# Servos.net
KiCad netlist of a schematic drawn in Altium Designer
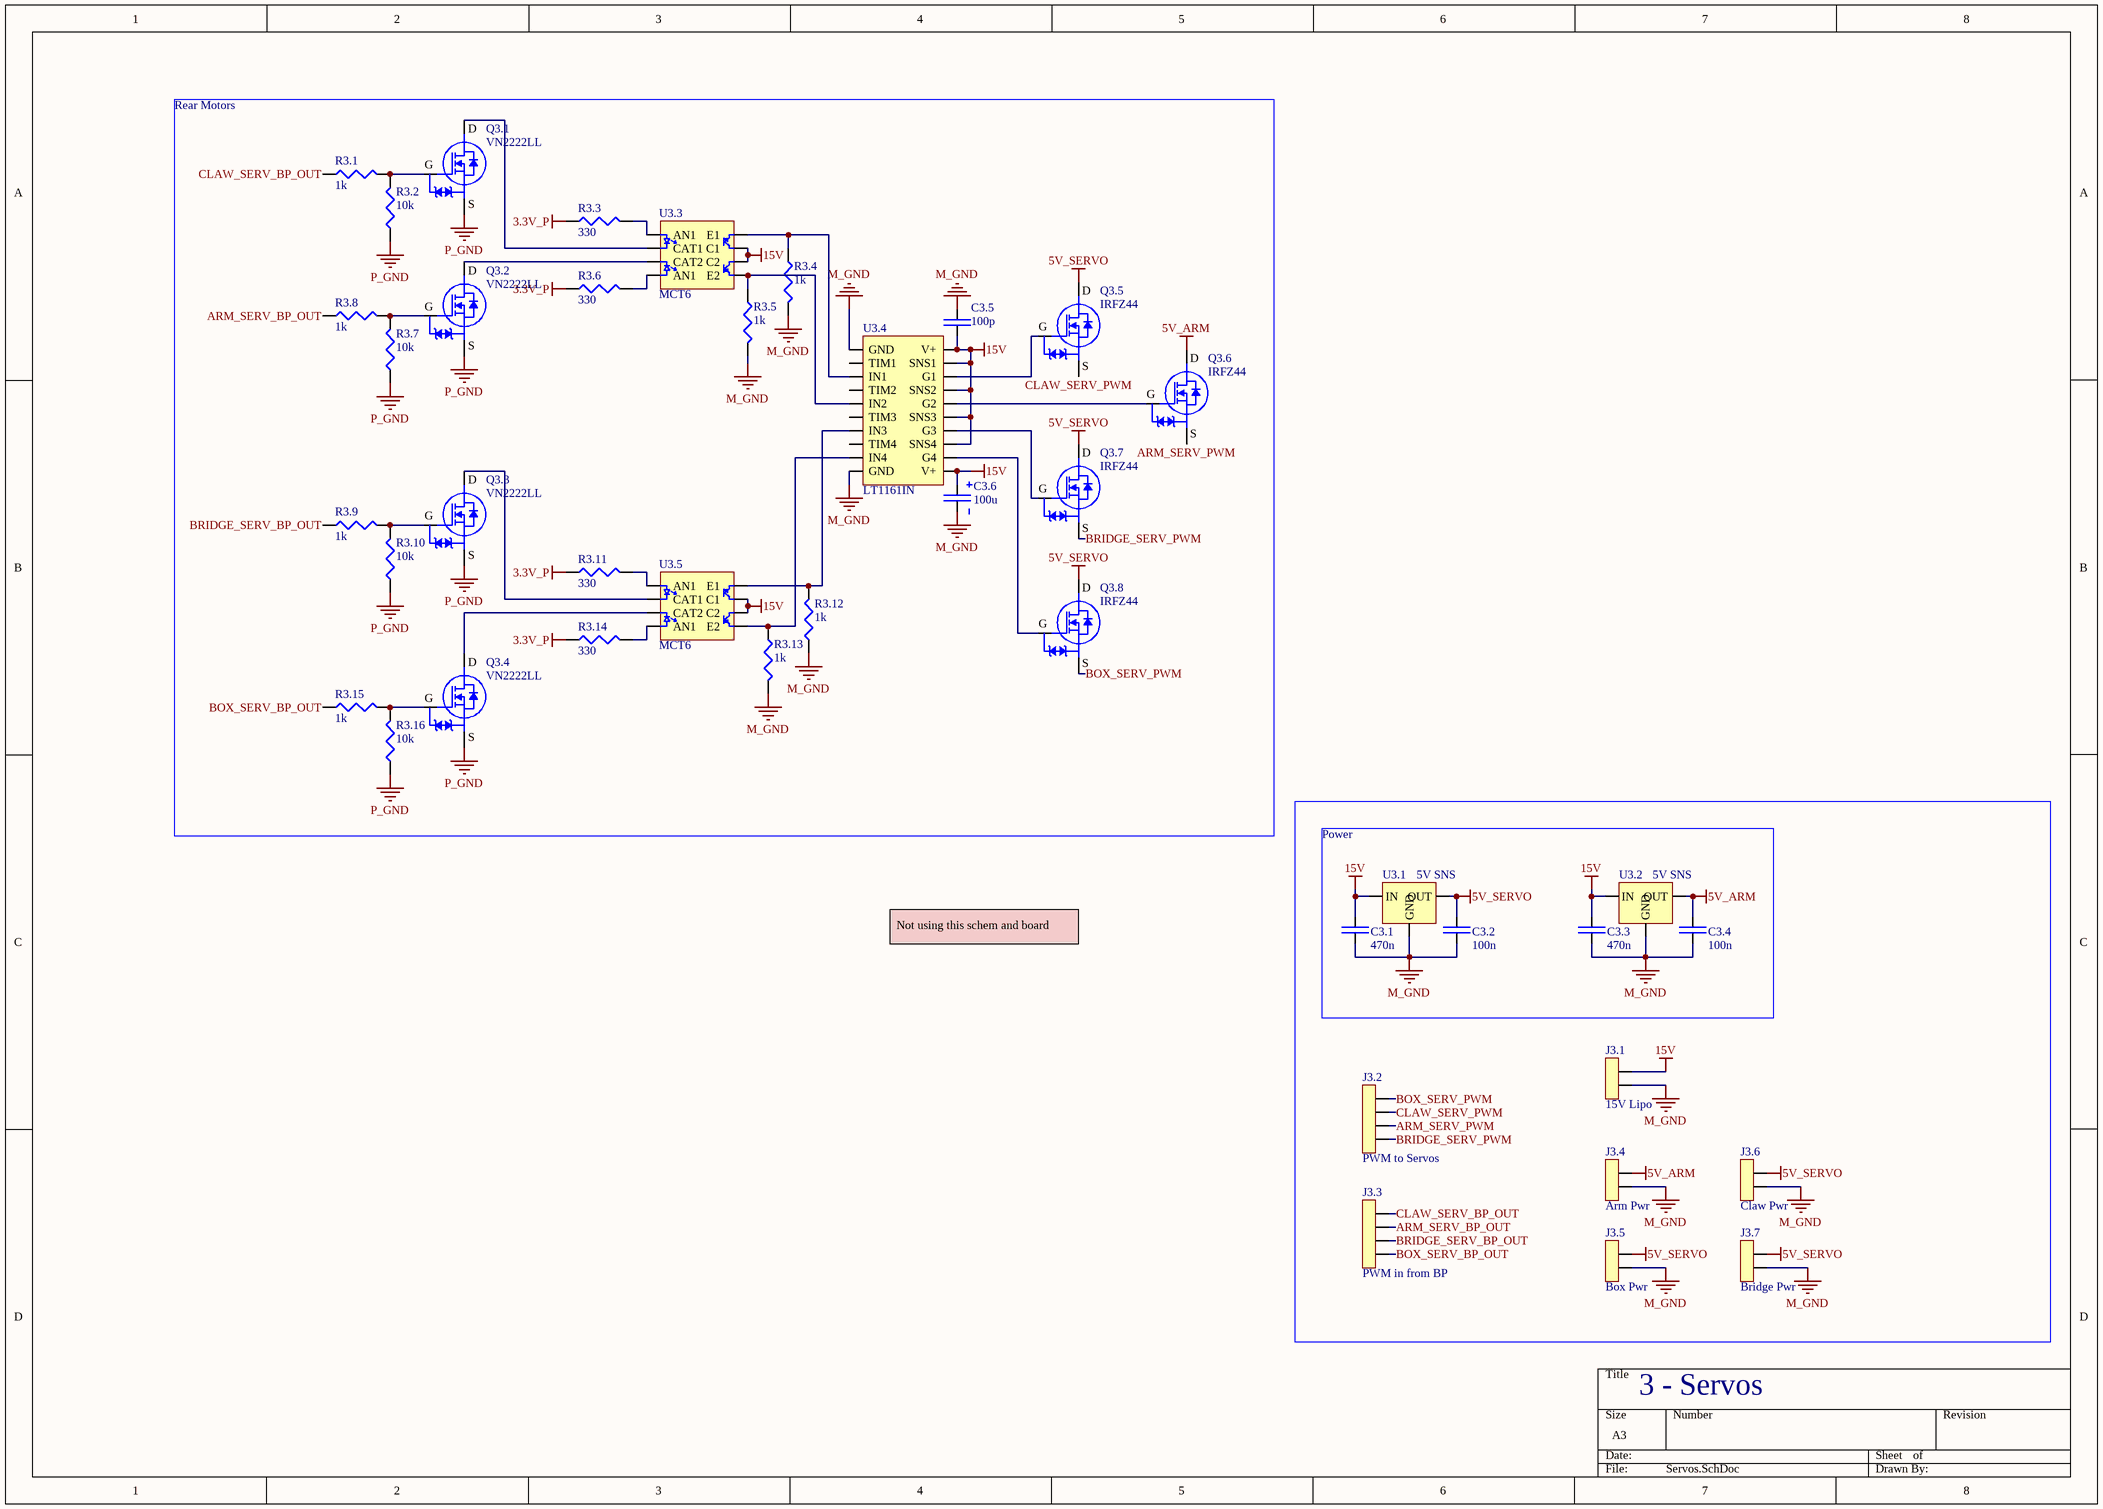
[diagram p0: Servos.SchDoc]

(export (version "E")
  (design (tool "Eeschema 10.0.6"))
  (components
    (comp (ref "C3.1")
      (value "470n")
      (footprint "Non Polarized Cap")
      (libsource (lib "SPICEBot_SchLib") (part "Cap_Generic"))
    )
    (comp (ref "C3.2")
      (value "100n")
      (footprint "Non Polarized Cap")
      (libsource (lib "SPICEBot_SchLib") (part "Cap_Generic"))
    )
    (comp (ref "C3.3")
      (value "470n")
      (footprint "Non Polarized Cap")
      (libsource (lib "SPICEBot_SchLib") (part "Cap_Generic"))
    )
    (comp (ref "C3.4")
      (value "100n")
      (footprint "Non Polarized Cap")
      (libsource (lib "SPICEBot_SchLib") (part "Cap_Generic"))
    )
    (comp (ref "C3.5")
      (value "100p")
      (footprint "Non Polarized Cap")
      (libsource (lib "SPICEBot_SchLib") (part "Cap_Generic"))
    )
    (comp (ref "C3.6")
      (value "100u")
      (footprint "Polarized Cap")
      (libsource (lib "SPICEBot_SchLib") (part "Polarized Cap"))
    )
    (comp (ref "J3.1")
      (value "15V Lipo")
      (footprint "2pos JST")
      (description "2pos Conn JST")
      (libsource (lib "SPICEBot_SchLib") (part "2pos Conn"))
    )
    (comp (ref "J3.2")
      (value "PWM to Servos")
      (footprint "4Pos JST")
      (description "4pos Conn")
      (libsource (lib "SPICEBot_SchLib") (part "4pos Conn"))
    )
    (comp (ref "J3.3")
      (value "PWM in from BP")
      (footprint "4Pos JST")
      (description "4pos Conn")
      (libsource (lib "SPICEBot_SchLib") (part "4pos Conn"))
    )
    (comp (ref "J3.4")
      (value "Arm Pwr")
      (footprint "2pos JST")
      (description "2pos Conn JST")
      (libsource (lib "SPICEBot_SchLib") (part "2pos Conn"))
    )
    (comp (ref "J3.5")
      (value "Box Pwr")
      (footprint "2pos JST")
      (description "2pos Conn JST")
      (libsource (lib "SPICEBot_SchLib") (part "2pos Conn"))
    )
    (comp (ref "J3.6")
      (value "Claw Pwr")
      (footprint "2pos JST")
      (description "2pos Conn JST")
      (libsource (lib "SPICEBot_SchLib") (part "2pos Conn"))
    )
    (comp (ref "J3.7")
      (value "Bridge Pwr")
      (footprint "2pos JST")
      (description "2pos Conn JST")
      (libsource (lib "SPICEBot_SchLib") (part "2pos Conn"))
    )
    (comp (ref "Q3.1")
      (value "VN2222LL")
      (footprint "VN2222LL")
      (description "VN2222LL N-Channel 60 V 150mA 400mW Through Hole TO-92 (TO-226)")
      (libsource (lib "SPICEBot_SchLib") (part "VN2222LL NMOS"))
    )
    (comp (ref "Q3.2")
      (value "VN2222LL")
      (footprint "VN2222LL")
      (description "VN2222LL N-Channel 60 V 150mA 400mW Through Hole TO-92 (TO-226)")
      (libsource (lib "SPICEBot_SchLib") (part "VN2222LL NMOS"))
    )
    (comp (ref "Q3.3")
      (value "VN2222LL")
      (footprint "VN2222LL")
      (description "VN2222LL N-Channel 60 V 150mA 400mW Through Hole TO-92 (TO-226)")
      (libsource (lib "SPICEBot_SchLib") (part "VN2222LL NMOS"))
    )
    (comp (ref "Q3.4")
      (value "VN2222LL")
      (footprint "VN2222LL")
      (description "VN2222LL N-Channel 60 V 150mA 400mW Through Hole TO-92 (TO-226)")
      (libsource (lib "SPICEBot_SchLib") (part "VN2222LL NMOS"))
    )
    (comp (ref "Q3.5")
      (value "IRFZ44")
      (footprint "TO220")
      (description "IRFZ44EPBF N-Channel 60 V 48A 110W Through Hole TO-220AB")
      (libsource (lib "SPICEBot_SchLib") (part "IRFZ44 NMOS"))
    )
    (comp (ref "Q3.6")
      (value "IRFZ44")
      (footprint "TO220")
      (description "IRFZ44EPBF N-Channel 60 V 48A 110W Through Hole TO-220AB")
      (libsource (lib "SPICEBot_SchLib") (part "IRFZ44 NMOS"))
    )
    (comp (ref "Q3.7")
      (value "IRFZ44")
      (footprint "TO220")
      (description "IRFZ44EPBF N-Channel 60 V 48A 110W Through Hole TO-220AB")
      (libsource (lib "SPICEBot_SchLib") (part "IRFZ44 NMOS"))
    )
    (comp (ref "Q3.8")
      (value "IRFZ44")
      (footprint "TO220")
      (description "IRFZ44EPBF N-Channel 60 V 48A 110W Through Hole TO-220AB")
      (libsource (lib "SPICEBot_SchLib") (part "IRFZ44 NMOS"))
    )
    (comp (ref "R3.1")
      (value "1k")
      (footprint "Res_Generic")
      (libsource (lib "SPICEBot_SchLib") (part "Res_Generic"))
    )
    (comp (ref "R3.2")
      (value "10k")
      (footprint "Res_Generic")
      (libsource (lib "SPICEBot_SchLib") (part "Res_Generic"))
    )
    (comp (ref "R3.3")
      (value "330")
      (footprint "Res_Generic")
      (libsource (lib "SPICEBot_SchLib") (part "Res_Generic"))
    )
    (comp (ref "R3.4")
      (value "1k")
      (footprint "Res_Generic")
      (libsource (lib "SPICEBot_SchLib") (part "Res_Generic"))
    )
    (comp (ref "R3.5")
      (value "1k")
      (footprint "Res_Generic")
      (libsource (lib "SPICEBot_SchLib") (part "Res_Generic"))
    )
    (comp (ref "R3.6")
      (value "330")
      (footprint "Res_Generic")
      (libsource (lib "SPICEBot_SchLib") (part "Res_Generic"))
    )
    (comp (ref "R3.7")
      (value "10k")
      (footprint "Res_Generic")
      (libsource (lib "SPICEBot_SchLib") (part "Res_Generic"))
    )
    (comp (ref "R3.8")
      (value "1k")
      (footprint "Res_Generic")
      (libsource (lib "SPICEBot_SchLib") (part "Res_Generic"))
    )
    (comp (ref "R3.9")
      (value "1k")
      (footprint "Res_Generic")
      (libsource (lib "SPICEBot_SchLib") (part "Res_Generic"))
    )
    (comp (ref "R3.10")
      (value "10k")
      (footprint "Res_Generic")
      (libsource (lib "SPICEBot_SchLib") (part "Res_Generic"))
    )
    (comp (ref "R3.11")
      (value "330")
      (footprint "Res_Generic")
      (libsource (lib "SPICEBot_SchLib") (part "Res_Generic"))
    )
    (comp (ref "R3.12")
      (value "1k")
      (footprint "Res_Generic")
      (libsource (lib "SPICEBot_SchLib") (part "Res_Generic"))
    )
    (comp (ref "R3.13")
      (value "1k")
      (footprint "Res_Generic")
      (libsource (lib "SPICEBot_SchLib") (part "Res_Generic"))
    )
    (comp (ref "R3.14")
      (value "330")
      (footprint "Res_Generic")
      (libsource (lib "SPICEBot_SchLib") (part "Res_Generic"))
    )
    (comp (ref "R3.15")
      (value "1k")
      (footprint "Res_Generic")
      (libsource (lib "SPICEBot_SchLib") (part "Res_Generic"))
    )
    (comp (ref "R3.16")
      (value "10k")
      (footprint "Res_Generic")
      (libsource (lib "SPICEBot_SchLib") (part "Res_Generic"))
    )
    (comp (ref "U3.1")
      (value "5V SNS")
      (footprint "TO220")
      (description "UA7805 IC REG LINEAR 5V 1.5A TO220-3")
      (libsource (lib "SPICEBot_SchLib") (part "UA7805 5V Reg"))
    )
    (comp (ref "U3.2")
      (value "5V SNS")
      (footprint "TO220")
      (description "UA7805 IC REG LINEAR 5V 1.5A TO220-3")
      (libsource (lib "SPICEBot_SchLib") (part "UA7805 5V Reg"))
    )
    (comp (ref "U3.3")
      (value "MCT6")
      (footprint "DIP8")
      (description "Optoisolator 5.3KV 2CH TRANS 8-DIP")
      (libsource (lib "SPICEBot_SchLib") (part "MCT6 Optocoupler"))
    )
    (comp (ref "U3.4")
      (value "LT1161IN")
      (footprint "DIP20")
      (description "LT1161IN High-Side Gate Driver IC Non-Inverting 20-PDIP")
      (libsource (lib "SPICEBot_SchLib") (part "LT1161IN Gate Driver"))
    )
    (comp (ref "U3.5")
      (value "MCT6")
      (footprint "DIP8")
      (description "Optoisolator 5.3KV 2CH TRANS 8-DIP")
      (libsource (lib "SPICEBot_SchLib") (part "MCT6 Optocoupler"))
    )
  )
  (nets
    (net (code "1") (name "/ARM_SERV_BP_OUT") (class "Default")
      (node (ref "J3.3") (pin "3") (pinfunction "3_3") (pintype "passive"))
      (node (ref "R3.8") (pin "1") (pinfunction "1_1") (pintype "passive"))
    )
    (net (code "2") (name "/ARM_SERV_PWM") (class "Default")
      (node (ref "J3.2") (pin "2") (pinfunction "2_2") (pintype "passive"))
      (node (ref "Q3.6") (pin "3") (pinfunction "S_3") (pintype "passive"))
    )
    (net (code "3") (name "/BOX_SERV_BP_OUT") (class "Default")
      (node (ref "J3.3") (pin "1") (pinfunction "1_1") (pintype "passive"))
      (node (ref "R3.15") (pin "1") (pinfunction "1_1") (pintype "passive"))
    )
    (net (code "4") (name "/BOX_SERV_PWM") (class "Default")
      (node (ref "J3.2") (pin "4") (pinfunction "4_4") (pintype "passive"))
      (node (ref "Q3.8") (pin "3") (pinfunction "S_3") (pintype "passive"))
    )
    (net (code "5") (name "/BRIDGE_SERV_BP_OUT") (class "Default")
      (node (ref "J3.3") (pin "2") (pinfunction "2_2") (pintype "passive"))
      (node (ref "R3.9") (pin "1") (pinfunction "1_1") (pintype "passive"))
    )
    (net (code "6") (name "/BRIDGE_SERV_PWM") (class "Default")
      (node (ref "J3.2") (pin "1") (pinfunction "1_1") (pintype "passive"))
      (node (ref "Q3.7") (pin "3") (pinfunction "S_3") (pintype "passive"))
    )
    (net (code "7") (name "/CLAW_SERV_BP_OUT") (class "Default")
      (node (ref "J3.3") (pin "4") (pinfunction "4_4") (pintype "passive"))
      (node (ref "R3.1") (pin "1") (pinfunction "1_1") (pintype "passive"))
    )
    (net (code "8") (name "/CLAW_SERV_PWM") (class "Default")
      (node (ref "J3.2") (pin "3") (pinfunction "3_3") (pintype "passive"))
      (node (ref "Q3.5") (pin "3") (pinfunction "S_3") (pintype "passive"))
    )
    (net (code "9") (name "3.3V_P") (class "Default")
      (node (ref "R3.11") (pin "1") (pinfunction "1_1") (pintype "passive"))
      (node (ref "R3.14") (pin "1") (pinfunction "1_1") (pintype "passive"))
      (node (ref "R3.3") (pin "1") (pinfunction "1_1") (pintype "passive"))
      (node (ref "R3.6") (pin "1") (pinfunction "1_1") (pintype "passive"))
    )
    (net (code "10") (name "5V_ARM") (class "Default")
      (node (ref "C3.4") (pin "2") (pinfunction "2_2") (pintype "passive"))
      (node (ref "J3.4") (pin "2") (pinfunction "2_2") (pintype "passive"))
      (node (ref "Q3.6") (pin "2") (pinfunction "D_2") (pintype "passive"))
      (node (ref "U3.2") (pin "3") (pinfunction "OUT_3") (pintype "passive"))
    )
    (net (code "11") (name "5V_SERVO") (class "Default")
      (node (ref "C3.2") (pin "2") (pinfunction "2_2") (pintype "passive"))
      (node (ref "J3.5") (pin "2") (pinfunction "2_2") (pintype "passive"))
      (node (ref "J3.6") (pin "2") (pinfunction "2_2") (pintype "passive"))
      (node (ref "J3.7") (pin "2") (pinfunction "2_2") (pintype "passive"))
      (node (ref "Q3.5") (pin "2") (pinfunction "D_2") (pintype "passive"))
      (node (ref "Q3.7") (pin "2") (pinfunction "D_2") (pintype "passive"))
      (node (ref "Q3.8") (pin "2") (pinfunction "D_2") (pintype "passive"))
      (node (ref "U3.1") (pin "3") (pinfunction "OUT_3") (pintype "passive"))
    )
    (net (code "12") (name "15V") (class "Default")
      (node (ref "C3.1") (pin "2") (pinfunction "2_2") (pintype "passive"))
      (node (ref "C3.3") (pin "2") (pinfunction "2_2") (pintype "passive"))
      (node (ref "C3.5") (pin "1") (pinfunction "1_1") (pintype "passive"))
      (node (ref "C3.6") (pin "1") (pinfunction "1_1") (pintype "passive"))
      (node (ref "J3.1") (pin "2") (pinfunction "2_2") (pintype "passive"))
      (node (ref "U3.1") (pin "1") (pinfunction "IN_1") (pintype "passive"))
      (node (ref "U3.2") (pin "1") (pinfunction "IN_1") (pintype "passive"))
      (node (ref "U3.3") (pin "6") (pinfunction "C2_6") (pintype "passive"))
      (node (ref "U3.3") (pin "7") (pinfunction "C1_7") (pintype "passive"))
      (node (ref "U3.4") (pin "11") (pinfunction "V+_11") (pintype "passive"))
      (node (ref "U3.4") (pin "13") (pinfunction "SNS4_13") (pintype "passive"))
      (node (ref "U3.4") (pin "15") (pinfunction "SNS3_15") (pintype "passive"))
      (node (ref "U3.4") (pin "17") (pinfunction "SNS2_17") (pintype "passive"))
      (node (ref "U3.4") (pin "19") (pinfunction "SNS1_19") (pintype "passive"))
      (node (ref "U3.4") (pin "20") (pinfunction "V+_20") (pintype "passive"))
      (node (ref "U3.5") (pin "6") (pinfunction "C2_6") (pintype "passive"))
      (node (ref "U3.5") (pin "7") (pinfunction "C1_7") (pintype "passive"))
    )
    (net (code "13") (name "M_GND") (class "Default")
      (node (ref "C3.1") (pin "1") (pinfunction "1_1") (pintype "passive"))
      (node (ref "C3.2") (pin "1") (pinfunction "1_1") (pintype "passive"))
      (node (ref "C3.3") (pin "1") (pinfunction "1_1") (pintype "passive"))
      (node (ref "C3.4") (pin "1") (pinfunction "1_1") (pintype "passive"))
      (node (ref "C3.5") (pin "2") (pinfunction "2_2") (pintype "passive"))
      (node (ref "C3.6") (pin "2") (pinfunction "2_2") (pintype "passive"))
      (node (ref "J3.1") (pin "1") (pinfunction "1_1") (pintype "passive"))
      (node (ref "J3.4") (pin "1") (pinfunction "1_1") (pintype "passive"))
      (node (ref "J3.5") (pin "1") (pinfunction "1_1") (pintype "passive"))
      (node (ref "J3.6") (pin "1") (pinfunction "1_1") (pintype "passive"))
      (node (ref "J3.7") (pin "1") (pinfunction "1_1") (pintype "passive"))
      (node (ref "R3.12") (pin "1") (pinfunction "1_1") (pintype "passive"))
      (node (ref "R3.13") (pin "2") (pinfunction "2_2") (pintype "passive"))
      (node (ref "R3.4") (pin "2") (pinfunction "2_2") (pintype "passive"))
      (node (ref "R3.5") (pin "2") (pinfunction "2_2") (pintype "passive"))
      (node (ref "U3.1") (pin "2") (pinfunction "GND_2") (pintype "passive"))
      (node (ref "U3.2") (pin "2") (pinfunction "GND_2") (pintype "passive"))
      (node (ref "U3.4") (pin "1") (pinfunction "GND_1") (pintype "passive"))
      (node (ref "U3.4") (pin "10") (pinfunction "GND_10") (pintype "passive"))
    )
    (net (code "14") (name "Net-(Q3.1-D)") (class "Default")
      (node (ref "Q3.1") (pin "3") (pinfunction "D_3") (pintype "passive"))
      (node (ref "U3.3") (pin "2") (pinfunction "CAT1_2") (pintype "passive"))
    )
    (net (code "15") (name "Net-(Q3.1-G)") (class "Default")
      (node (ref "Q3.1") (pin "2") (pinfunction "G_2") (pintype "passive"))
      (node (ref "R3.1") (pin "2") (pinfunction "2_2") (pintype "passive"))
      (node (ref "R3.2") (pin "2") (pinfunction "2_2") (pintype "passive"))
    )
    (net (code "16") (name "Net-(Q3.2-D)") (class "Default")
      (node (ref "Q3.2") (pin "3") (pinfunction "D_3") (pintype "passive"))
      (node (ref "U3.3") (pin "3") (pinfunction "CAT2_3") (pintype "passive"))
    )
    (net (code "17") (name "Net-(Q3.2-G)") (class "Default")
      (node (ref "Q3.2") (pin "2") (pinfunction "G_2") (pintype "passive"))
      (node (ref "R3.7") (pin "2") (pinfunction "2_2") (pintype "passive"))
      (node (ref "R3.8") (pin "2") (pinfunction "2_2") (pintype "passive"))
    )
    (net (code "18") (name "Net-(Q3.3-D)") (class "Default")
      (node (ref "Q3.3") (pin "3") (pinfunction "D_3") (pintype "passive"))
      (node (ref "U3.5") (pin "2") (pinfunction "CAT1_2") (pintype "passive"))
    )
    (net (code "19") (name "Net-(Q3.3-G)") (class "Default")
      (node (ref "Q3.3") (pin "2") (pinfunction "G_2") (pintype "passive"))
      (node (ref "R3.10") (pin "2") (pinfunction "2_2") (pintype "passive"))
      (node (ref "R3.9") (pin "2") (pinfunction "2_2") (pintype "passive"))
    )
    (net (code "20") (name "Net-(Q3.4-D)") (class "Default")
      (node (ref "Q3.4") (pin "3") (pinfunction "D_3") (pintype "passive"))
      (node (ref "U3.5") (pin "3") (pinfunction "CAT2_3") (pintype "passive"))
    )
    (net (code "21") (name "Net-(Q3.4-G)") (class "Default")
      (node (ref "Q3.4") (pin "2") (pinfunction "G_2") (pintype "passive"))
      (node (ref "R3.15") (pin "2") (pinfunction "2_2") (pintype "passive"))
      (node (ref "R3.16") (pin "2") (pinfunction "2_2") (pintype "passive"))
    )
    (net (code "22") (name "Net-(Q3.5-G)") (class "Default")
      (node (ref "Q3.5") (pin "1") (pinfunction "G_1") (pintype "passive"))
      (node (ref "U3.4") (pin "18") (pinfunction "G1_18") (pintype "passive"))
    )
    (net (code "23") (name "Net-(Q3.6-G)") (class "Default")
      (node (ref "Q3.6") (pin "1") (pinfunction "G_1") (pintype "passive"))
      (node (ref "U3.4") (pin "16") (pinfunction "G2_16") (pintype "passive"))
    )
    (net (code "24") (name "Net-(Q3.7-G)") (class "Default")
      (node (ref "Q3.7") (pin "1") (pinfunction "G_1") (pintype "passive"))
      (node (ref "U3.4") (pin "14") (pinfunction "G3_14") (pintype "passive"))
    )
    (net (code "25") (name "Net-(Q3.8-G)") (class "Default")
      (node (ref "Q3.8") (pin "1") (pinfunction "G_1") (pintype "passive"))
      (node (ref "U3.4") (pin "12") (pinfunction "G4_12") (pintype "passive"))
    )
    (net (code "26") (name "Net-(R3.3-Pad2)") (class "Default")
      (node (ref "R3.3") (pin "2") (pinfunction "2_2") (pintype "passive"))
      (node (ref "U3.3") (pin "1") (pinfunction "AN1_1") (pintype "passive"))
    )
    (net (code "27") (name "Net-(R3.6-Pad2)") (class "Default")
      (node (ref "R3.6") (pin "2") (pinfunction "2_2") (pintype "passive"))
      (node (ref "U3.3") (pin "4") (pinfunction "AN1_4") (pintype "passive"))
    )
    (net (code "28") (name "Net-(R3.11-Pad2)") (class "Default")
      (node (ref "R3.11") (pin "2") (pinfunction "2_2") (pintype "passive"))
      (node (ref "U3.5") (pin "1") (pinfunction "AN1_1") (pintype "passive"))
    )
    (net (code "29") (name "Net-(R3.14-Pad2)") (class "Default")
      (node (ref "R3.14") (pin "2") (pinfunction "2_2") (pintype "passive"))
      (node (ref "U3.5") (pin "4") (pinfunction "AN1_4") (pintype "passive"))
    )
    (net (code "30") (name "Net-(U3.3-E1)") (class "Default")
      (node (ref "R3.4") (pin "1") (pinfunction "1_1") (pintype "passive"))
      (node (ref "U3.3") (pin "8") (pinfunction "E1_8") (pintype "passive"))
      (node (ref "U3.4") (pin "3") (pinfunction "IN1_3") (pintype "passive"))
    )
    (net (code "31") (name "Net-(U3.3-E2)") (class "Default")
      (node (ref "R3.5") (pin "1") (pinfunction "1_1") (pintype "passive"))
      (node (ref "U3.3") (pin "5") (pinfunction "E2_5") (pintype "passive"))
      (node (ref "U3.4") (pin "5") (pinfunction "IN2_5") (pintype "passive"))
    )
    (net (code "32") (name "Net-(U3.4-IN3)") (class "Default")
      (node (ref "R3.12") (pin "2") (pinfunction "2_2") (pintype "passive"))
      (node (ref "U3.4") (pin "7") (pinfunction "IN3_7") (pintype "passive"))
      (node (ref "U3.5") (pin "8") (pinfunction "E1_8") (pintype "passive"))
    )
    (net (code "33") (name "Net-(U3.4-IN4)") (class "Default")
      (node (ref "R3.13") (pin "1") (pinfunction "1_1") (pintype "passive"))
      (node (ref "U3.4") (pin "9") (pinfunction "IN4_9") (pintype "passive"))
      (node (ref "U3.5") (pin "5") (pinfunction "E2_5") (pintype "passive"))
    )
    (net (code "34") (name "P_GND") (class "Default")
      (node (ref "Q3.1") (pin "1") (pinfunction "S_1") (pintype "passive"))
      (node (ref "Q3.2") (pin "1") (pinfunction "S_1") (pintype "passive"))
      (node (ref "Q3.3") (pin "1") (pinfunction "S_1") (pintype "passive"))
      (node (ref "Q3.4") (pin "1") (pinfunction "S_1") (pintype "passive"))
      (node (ref "R3.10") (pin "1") (pinfunction "1_1") (pintype "passive"))
      (node (ref "R3.16") (pin "1") (pinfunction "1_1") (pintype "passive"))
      (node (ref "R3.2") (pin "1") (pinfunction "1_1") (pintype "passive"))
      (node (ref "R3.7") (pin "1") (pinfunction "1_1") (pintype "passive"))
    )
    (net (code "35") (name "unconnected-(U3.4-TIM1-Pad2)") (class "Default")
      (node (ref "U3.4") (pin "2") (pinfunction "TIM1_2") (pintype "passive"))
    )
    (net (code "36") (name "unconnected-(U3.4-TIM2-Pad4)") (class "Default")
      (node (ref "U3.4") (pin "4") (pinfunction "TIM2_4") (pintype "passive"))
    )
    (net (code "37") (name "unconnected-(U3.4-TIM3-Pad6)") (class "Default")
      (node (ref "U3.4") (pin "6") (pinfunction "TIM3_6") (pintype "passive"))
    )
    (net (code "38") (name "unconnected-(U3.4-TIM4-Pad8)") (class "Default")
      (node (ref "U3.4") (pin "8") (pinfunction "TIM4_8") (pintype "passive"))
    )
  )
)
